# harpscheme.net
KiCad netlist of a schematic drawn in EAGLE
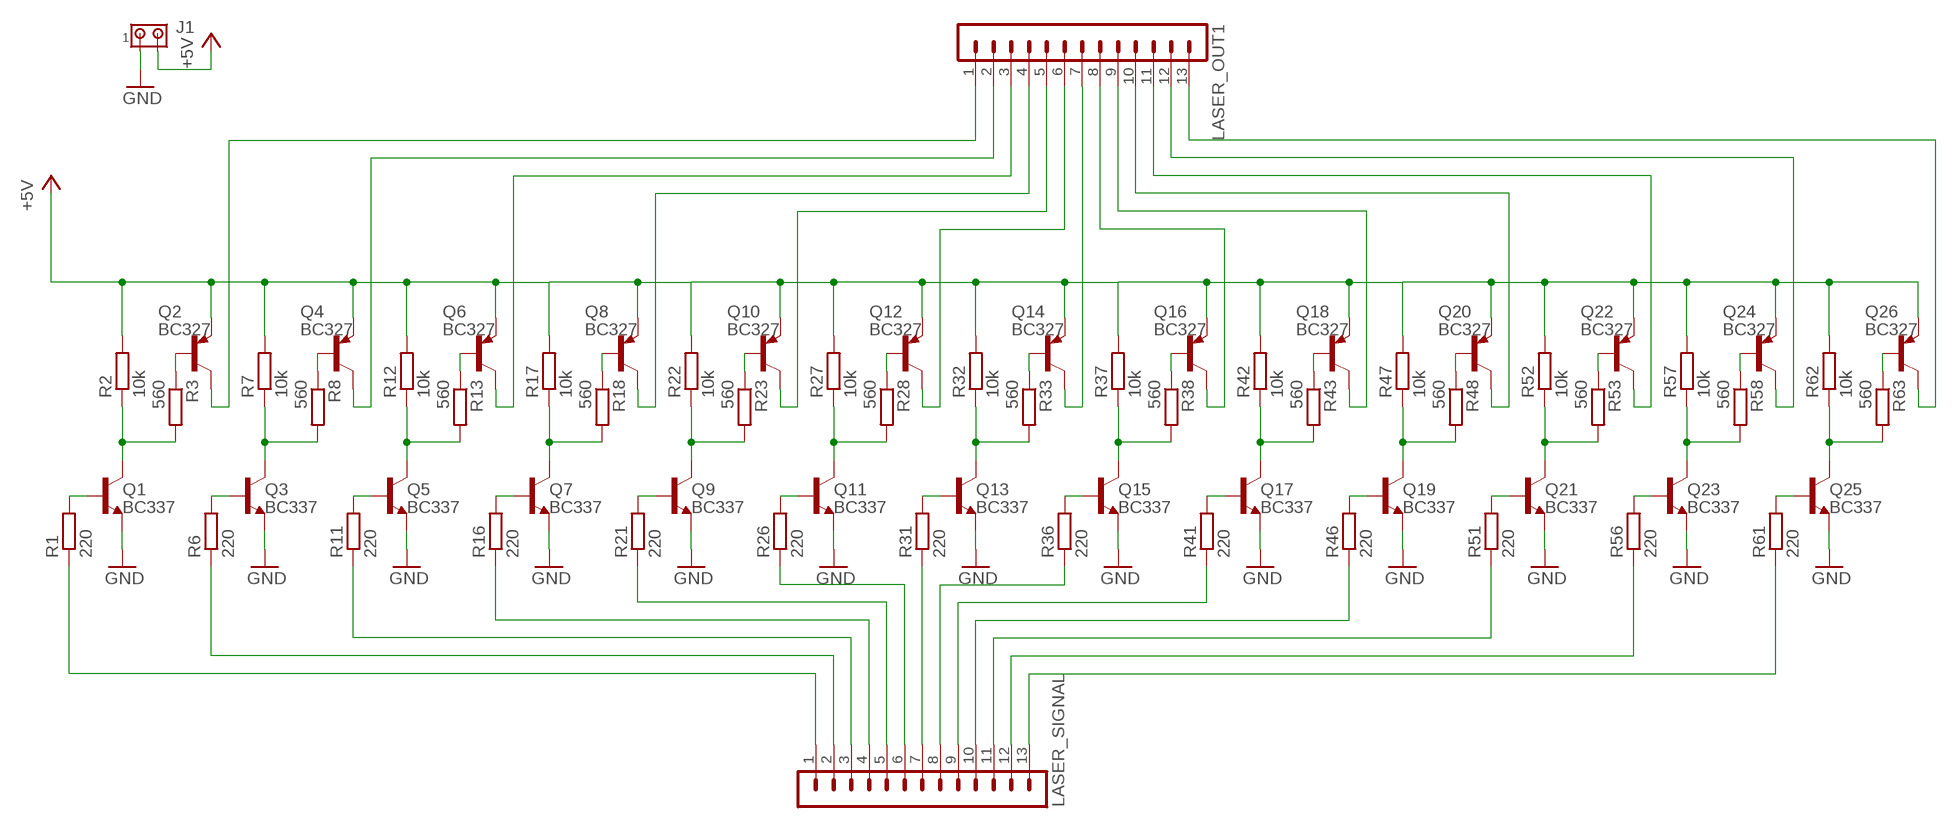
[diagram p0: schematic, sheet 1]

(export (version "E")
  (design (tool "Eeschema 10.0.6"))
  (components
    (comp (ref "J1")
      (value "MTA02-100")
      (footprint "eagle-import:10X02MTA")
      (libsource (lib "eagle-import") (part "MTA02-100"))
    )
    (comp (ref "LASER_OUT1")
      (value "MA13-1")
      (footprint "eagle-import:MA13-1")
      (libsource (lib "eagle-import") (part "MA13-1"))
    )
    (comp (ref "LASER_SIGNAL")
      (value "MA13-1")
      (footprint "eagle-import:MA13-1")
      (libsource (lib "eagle-import") (part "MA13-1"))
    )
    (comp (ref "Q1")
      (value "BC337")
      (footprint "eagle-import:TO92")
      (libsource (lib "eagle-import") (part "BC337"))
    )
    (comp (ref "Q2")
      (value "BC327")
      (footprint "eagle-import:TO92-EBC")
      (libsource (lib "eagle-import") (part "BC327"))
    )
    (comp (ref "Q3")
      (value "BC337")
      (footprint "eagle-import:TO92")
      (libsource (lib "eagle-import") (part "BC337"))
    )
    (comp (ref "Q4")
      (value "BC327")
      (footprint "eagle-import:TO92-EBC")
      (libsource (lib "eagle-import") (part "BC327"))
    )
    (comp (ref "Q5")
      (value "BC337")
      (footprint "eagle-import:TO92")
      (libsource (lib "eagle-import") (part "BC337"))
    )
    (comp (ref "Q6")
      (value "BC327")
      (footprint "eagle-import:TO92-EBC")
      (libsource (lib "eagle-import") (part "BC327"))
    )
    (comp (ref "Q7")
      (value "BC337")
      (footprint "eagle-import:TO92")
      (libsource (lib "eagle-import") (part "BC337"))
    )
    (comp (ref "Q8")
      (value "BC327")
      (footprint "eagle-import:TO92-EBC")
      (libsource (lib "eagle-import") (part "BC327"))
    )
    (comp (ref "Q9")
      (value "BC337")
      (footprint "eagle-import:TO92")
      (libsource (lib "eagle-import") (part "BC337"))
    )
    (comp (ref "Q10")
      (value "BC327")
      (footprint "eagle-import:TO92-EBC")
      (libsource (lib "eagle-import") (part "BC327"))
    )
    (comp (ref "Q11")
      (value "BC337")
      (footprint "eagle-import:TO92")
      (libsource (lib "eagle-import") (part "BC337"))
    )
    (comp (ref "Q12")
      (value "BC327")
      (footprint "eagle-import:TO92-EBC")
      (libsource (lib "eagle-import") (part "BC327"))
    )
    (comp (ref "Q13")
      (value "BC337")
      (footprint "eagle-import:TO92")
      (libsource (lib "eagle-import") (part "BC337"))
    )
    (comp (ref "Q14")
      (value "BC327")
      (footprint "eagle-import:TO92-EBC")
      (libsource (lib "eagle-import") (part "BC327"))
    )
    (comp (ref "Q15")
      (value "BC337")
      (footprint "eagle-import:TO92")
      (libsource (lib "eagle-import") (part "BC337"))
    )
    (comp (ref "Q16")
      (value "BC327")
      (footprint "eagle-import:TO92-EBC")
      (libsource (lib "eagle-import") (part "BC327"))
    )
    (comp (ref "Q17")
      (value "BC337")
      (footprint "eagle-import:TO92")
      (libsource (lib "eagle-import") (part "BC337"))
    )
    (comp (ref "Q18")
      (value "BC327")
      (footprint "eagle-import:TO92-EBC")
      (libsource (lib "eagle-import") (part "BC327"))
    )
    (comp (ref "Q19")
      (value "BC337")
      (footprint "eagle-import:TO92")
      (libsource (lib "eagle-import") (part "BC337"))
    )
    (comp (ref "Q20")
      (value "BC327")
      (footprint "eagle-import:TO92-EBC")
      (libsource (lib "eagle-import") (part "BC327"))
    )
    (comp (ref "Q21")
      (value "BC337")
      (footprint "eagle-import:TO92")
      (libsource (lib "eagle-import") (part "BC337"))
    )
    (comp (ref "Q22")
      (value "BC327")
      (footprint "eagle-import:TO92-EBC")
      (libsource (lib "eagle-import") (part "BC327"))
    )
    (comp (ref "Q23")
      (value "BC337")
      (footprint "eagle-import:TO92")
      (libsource (lib "eagle-import") (part "BC337"))
    )
    (comp (ref "Q24")
      (value "BC327")
      (footprint "eagle-import:TO92-EBC")
      (libsource (lib "eagle-import") (part "BC327"))
    )
    (comp (ref "Q25")
      (value "BC337")
      (footprint "eagle-import:TO92")
      (libsource (lib "eagle-import") (part "BC337"))
    )
    (comp (ref "Q26")
      (value "BC327")
      (footprint "eagle-import:TO92-EBC")
      (libsource (lib "eagle-import") (part "BC327"))
    )
    (comp (ref "R1")
      (value "220")
      (footprint "eagle-import:0207_7")
      (libsource (lib "eagle-import") (part "R-EU_0207/7"))
    )
    (comp (ref "R2")
      (value "10k")
      (footprint "eagle-import:0207_7")
      (libsource (lib "eagle-import") (part "R-EU_0207/7"))
    )
    (comp (ref "R3")
      (value "560")
      (footprint "eagle-import:0207_7")
      (libsource (lib "eagle-import") (part "R-EU_0207/7"))
    )
    (comp (ref "R6")
      (value "220")
      (footprint "eagle-import:0207_7")
      (libsource (lib "eagle-import") (part "R-EU_0207/7"))
    )
    (comp (ref "R7")
      (value "10k")
      (footprint "eagle-import:0207_7")
      (libsource (lib "eagle-import") (part "R-EU_0207/7"))
    )
    (comp (ref "R8")
      (value "560")
      (footprint "eagle-import:0207_7")
      (libsource (lib "eagle-import") (part "R-EU_0207/7"))
    )
    (comp (ref "R11")
      (value "220")
      (footprint "eagle-import:0207_7")
      (libsource (lib "eagle-import") (part "R-EU_0207/7"))
    )
    (comp (ref "R12")
      (value "10k")
      (footprint "eagle-import:0207_7")
      (libsource (lib "eagle-import") (part "R-EU_0207/7"))
    )
    (comp (ref "R13")
      (value "560")
      (footprint "eagle-import:0207_7")
      (libsource (lib "eagle-import") (part "R-EU_0207/7"))
    )
    (comp (ref "R16")
      (value "220")
      (footprint "eagle-import:0207_7")
      (libsource (lib "eagle-import") (part "R-EU_0207/7"))
    )
    (comp (ref "R17")
      (value "10k")
      (footprint "eagle-import:0207_7")
      (libsource (lib "eagle-import") (part "R-EU_0207/7"))
    )
    (comp (ref "R18")
      (value "560")
      (footprint "eagle-import:0207_7")
      (libsource (lib "eagle-import") (part "R-EU_0207/7"))
    )
    (comp (ref "R21")
      (value "220")
      (footprint "eagle-import:0207_7")
      (libsource (lib "eagle-import") (part "R-EU_0207/7"))
    )
    (comp (ref "R22")
      (value "10k")
      (footprint "eagle-import:0207_7")
      (libsource (lib "eagle-import") (part "R-EU_0207/7"))
    )
    (comp (ref "R23")
      (value "560")
      (footprint "eagle-import:0207_7")
      (libsource (lib "eagle-import") (part "R-EU_0207/7"))
    )
    (comp (ref "R26")
      (value "220")
      (footprint "eagle-import:0207_7")
      (libsource (lib "eagle-import") (part "R-EU_0207/7"))
    )
    (comp (ref "R27")
      (value "10k")
      (footprint "eagle-import:0207_7")
      (libsource (lib "eagle-import") (part "R-EU_0207/7"))
    )
    (comp (ref "R28")
      (value "560")
      (footprint "eagle-import:0207_7")
      (libsource (lib "eagle-import") (part "R-EU_0207/7"))
    )
    (comp (ref "R31")
      (value "220")
      (footprint "eagle-import:0207_7")
      (libsource (lib "eagle-import") (part "R-EU_0207/7"))
    )
    (comp (ref "R32")
      (value "10k")
      (footprint "eagle-import:0207_7")
      (libsource (lib "eagle-import") (part "R-EU_0207/7"))
    )
    (comp (ref "R33")
      (value "560")
      (footprint "eagle-import:0207_7")
      (libsource (lib "eagle-import") (part "R-EU_0207/7"))
    )
    (comp (ref "R36")
      (value "220")
      (footprint "eagle-import:0207_7")
      (libsource (lib "eagle-import") (part "R-EU_0207/7"))
    )
    (comp (ref "R37")
      (value "10k")
      (footprint "eagle-import:0207_7")
      (libsource (lib "eagle-import") (part "R-EU_0207/7"))
    )
    (comp (ref "R38")
      (value "560")
      (footprint "eagle-import:0207_7")
      (libsource (lib "eagle-import") (part "R-EU_0207/7"))
    )
    (comp (ref "R41")
      (value "220")
      (footprint "eagle-import:0207_7")
      (libsource (lib "eagle-import") (part "R-EU_0207/7"))
    )
    (comp (ref "R42")
      (value "10k")
      (footprint "eagle-import:0207_7")
      (libsource (lib "eagle-import") (part "R-EU_0207/7"))
    )
    (comp (ref "R43")
      (value "560")
      (footprint "eagle-import:0207_7")
      (libsource (lib "eagle-import") (part "R-EU_0207/7"))
    )
    (comp (ref "R46")
      (value "220")
      (footprint "eagle-import:0207_7")
      (libsource (lib "eagle-import") (part "R-EU_0207/7"))
    )
    (comp (ref "R47")
      (value "10k")
      (footprint "eagle-import:0207_7")
      (libsource (lib "eagle-import") (part "R-EU_0207/7"))
    )
    (comp (ref "R48")
      (value "560")
      (footprint "eagle-import:0207_7")
      (libsource (lib "eagle-import") (part "R-EU_0207/7"))
    )
    (comp (ref "R51")
      (value "220")
      (footprint "eagle-import:0207_7")
      (libsource (lib "eagle-import") (part "R-EU_0207/7"))
    )
    (comp (ref "R52")
      (value "10k")
      (footprint "eagle-import:0207_7")
      (libsource (lib "eagle-import") (part "R-EU_0207/7"))
    )
    (comp (ref "R53")
      (value "560")
      (footprint "eagle-import:0207_7")
      (libsource (lib "eagle-import") (part "R-EU_0207/7"))
    )
    (comp (ref "R56")
      (value "220")
      (footprint "eagle-import:0207_7")
      (libsource (lib "eagle-import") (part "R-EU_0207/7"))
    )
    (comp (ref "R57")
      (value "10k")
      (footprint "eagle-import:0207_7")
      (libsource (lib "eagle-import") (part "R-EU_0207/7"))
    )
    (comp (ref "R58")
      (value "560")
      (footprint "eagle-import:0207_7")
      (libsource (lib "eagle-import") (part "R-EU_0207/7"))
    )
    (comp (ref "R61")
      (value "220")
      (footprint "eagle-import:0207_7")
      (libsource (lib "eagle-import") (part "R-EU_0207/7"))
    )
    (comp (ref "R62")
      (value "10k")
      (footprint "eagle-import:0207_7")
      (libsource (lib "eagle-import") (part "R-EU_0207/7"))
    )
    (comp (ref "R63")
      (value "560")
      (footprint "eagle-import:0207_7")
      (libsource (lib "eagle-import") (part "R-EU_0207/7"))
    )
  )
  (nets
    (net (code "1") (name "+5V") (class "Default")
      (node (ref "J1") (pin "2") (pinfunction "2_2") (pintype "passive"))
      (node (ref "Q10") (pin "E") (pinfunction "E_E") (pintype "passive"))
      (node (ref "Q12") (pin "E") (pinfunction "E_E") (pintype "passive"))
      (node (ref "Q14") (pin "E") (pinfunction "E_E") (pintype "passive"))
      (node (ref "Q16") (pin "E") (pinfunction "E_E") (pintype "passive"))
      (node (ref "Q18") (pin "E") (pinfunction "E_E") (pintype "passive"))
      (node (ref "Q2") (pin "E") (pinfunction "E_E") (pintype "passive"))
      (node (ref "Q20") (pin "E") (pinfunction "E_E") (pintype "passive"))
      (node (ref "Q22") (pin "E") (pinfunction "E_E") (pintype "passive"))
      (node (ref "Q24") (pin "E") (pinfunction "E_E") (pintype "passive"))
      (node (ref "Q26") (pin "E") (pinfunction "E_E") (pintype "passive"))
      (node (ref "Q4") (pin "E") (pinfunction "E_E") (pintype "passive"))
      (node (ref "Q6") (pin "E") (pinfunction "E_E") (pintype "passive"))
      (node (ref "Q8") (pin "E") (pinfunction "E_E") (pintype "passive"))
      (node (ref "R12") (pin "2") (pinfunction "2_2") (pintype "passive"))
      (node (ref "R17") (pin "2") (pinfunction "2_2") (pintype "passive"))
      (node (ref "R2") (pin "2") (pinfunction "2_2") (pintype "passive"))
      (node (ref "R22") (pin "2") (pinfunction "2_2") (pintype "passive"))
      (node (ref "R27") (pin "2") (pinfunction "2_2") (pintype "passive"))
      (node (ref "R32") (pin "2") (pinfunction "2_2") (pintype "passive"))
      (node (ref "R37") (pin "2") (pinfunction "2_2") (pintype "passive"))
      (node (ref "R42") (pin "2") (pinfunction "2_2") (pintype "passive"))
      (node (ref "R47") (pin "2") (pinfunction "2_2") (pintype "passive"))
      (node (ref "R52") (pin "2") (pinfunction "2_2") (pintype "passive"))
      (node (ref "R57") (pin "2") (pinfunction "2_2") (pintype "passive"))
      (node (ref "R62") (pin "2") (pinfunction "2_2") (pintype "passive"))
      (node (ref "R7") (pin "2") (pinfunction "2_2") (pintype "passive"))
    )
    (net (code "2") (name "GND") (class "Default")
      (node (ref "J1") (pin "1") (pinfunction "1_1") (pintype "passive"))
      (node (ref "Q1") (pin "1") (pinfunction "E_1") (pintype "passive"))
      (node (ref "Q11") (pin "1") (pinfunction "E_1") (pintype "passive"))
      (node (ref "Q13") (pin "1") (pinfunction "E_1") (pintype "passive"))
      (node (ref "Q15") (pin "1") (pinfunction "E_1") (pintype "passive"))
      (node (ref "Q17") (pin "1") (pinfunction "E_1") (pintype "passive"))
      (node (ref "Q19") (pin "1") (pinfunction "E_1") (pintype "passive"))
      (node (ref "Q21") (pin "1") (pinfunction "E_1") (pintype "passive"))
      (node (ref "Q23") (pin "1") (pinfunction "E_1") (pintype "passive"))
      (node (ref "Q25") (pin "1") (pinfunction "E_1") (pintype "passive"))
      (node (ref "Q3") (pin "1") (pinfunction "E_1") (pintype "passive"))
      (node (ref "Q5") (pin "1") (pinfunction "E_1") (pintype "passive"))
      (node (ref "Q7") (pin "1") (pinfunction "E_1") (pintype "passive"))
      (node (ref "Q9") (pin "1") (pinfunction "E_1") (pintype "passive"))
    )
    (net (code "3") (name "Net-(LASER_OUT1-Pad1)") (class "Default")
      (node (ref "LASER_OUT1") (pin "1") (pinfunction "1_1") (pintype "passive"))
      (node (ref "Q2") (pin "C") (pinfunction "C_C") (pintype "passive"))
    )
    (net (code "4") (name "Net-(LASER_OUT1-Pad2)") (class "Default")
      (node (ref "LASER_OUT1") (pin "2") (pinfunction "2_2") (pintype "passive"))
      (node (ref "Q4") (pin "C") (pinfunction "C_C") (pintype "passive"))
    )
    (net (code "5") (name "Net-(LASER_OUT1-Pad3)") (class "Default")
      (node (ref "LASER_OUT1") (pin "3") (pinfunction "3_3") (pintype "passive"))
      (node (ref "Q6") (pin "C") (pinfunction "C_C") (pintype "passive"))
    )
    (net (code "6") (name "Net-(LASER_OUT1-Pad4)") (class "Default")
      (node (ref "LASER_OUT1") (pin "4") (pinfunction "4_4") (pintype "passive"))
      (node (ref "Q8") (pin "C") (pinfunction "C_C") (pintype "passive"))
    )
    (net (code "7") (name "Net-(LASER_OUT1-Pad5)") (class "Default")
      (node (ref "LASER_OUT1") (pin "5") (pinfunction "5_5") (pintype "passive"))
      (node (ref "Q10") (pin "C") (pinfunction "C_C") (pintype "passive"))
    )
    (net (code "8") (name "Net-(LASER_OUT1-Pad6)") (class "Default")
      (node (ref "LASER_OUT1") (pin "6") (pinfunction "6_6") (pintype "passive"))
      (node (ref "Q12") (pin "C") (pinfunction "C_C") (pintype "passive"))
    )
    (net (code "9") (name "Net-(LASER_OUT1-Pad7)") (class "Default")
      (node (ref "LASER_OUT1") (pin "7") (pinfunction "7_7") (pintype "passive"))
      (node (ref "Q14") (pin "C") (pinfunction "C_C") (pintype "passive"))
    )
    (net (code "10") (name "Net-(LASER_OUT1-Pad8)") (class "Default")
      (node (ref "LASER_OUT1") (pin "8") (pinfunction "8_8") (pintype "passive"))
      (node (ref "Q16") (pin "C") (pinfunction "C_C") (pintype "passive"))
    )
    (net (code "11") (name "Net-(LASER_OUT1-Pad9)") (class "Default")
      (node (ref "LASER_OUT1") (pin "9") (pinfunction "9_9") (pintype "passive"))
      (node (ref "Q18") (pin "C") (pinfunction "C_C") (pintype "passive"))
    )
    (net (code "12") (name "Net-(LASER_OUT1-Pad10)") (class "Default")
      (node (ref "LASER_OUT1") (pin "10") (pinfunction "10_10") (pintype "passive"))
      (node (ref "Q20") (pin "C") (pinfunction "C_C") (pintype "passive"))
    )
    (net (code "13") (name "Net-(LASER_OUT1-Pad11)") (class "Default")
      (node (ref "LASER_OUT1") (pin "11") (pinfunction "11_11") (pintype "passive"))
      (node (ref "Q22") (pin "C") (pinfunction "C_C") (pintype "passive"))
    )
    (net (code "14") (name "Net-(LASER_OUT1-Pad12)") (class "Default")
      (node (ref "LASER_OUT1") (pin "12") (pinfunction "12_12") (pintype "passive"))
      (node (ref "Q24") (pin "C") (pinfunction "C_C") (pintype "passive"))
    )
    (net (code "15") (name "Net-(LASER_OUT1-Pad13)") (class "Default")
      (node (ref "LASER_OUT1") (pin "13") (pinfunction "13_13") (pintype "passive"))
      (node (ref "Q26") (pin "C") (pinfunction "C_C") (pintype "passive"))
    )
    (net (code "16") (name "Net-(LASER_SIGNAL-Pad1)") (class "Default")
      (node (ref "LASER_SIGNAL") (pin "1") (pinfunction "1_1") (pintype "passive"))
      (node (ref "R1") (pin "1") (pinfunction "1_1") (pintype "passive"))
    )
    (net (code "17") (name "Net-(LASER_SIGNAL-Pad2)") (class "Default")
      (node (ref "LASER_SIGNAL") (pin "2") (pinfunction "2_2") (pintype "passive"))
      (node (ref "R6") (pin "1") (pinfunction "1_1") (pintype "passive"))
    )
    (net (code "18") (name "Net-(LASER_SIGNAL-Pad3)") (class "Default")
      (node (ref "LASER_SIGNAL") (pin "3") (pinfunction "3_3") (pintype "passive"))
      (node (ref "R11") (pin "1") (pinfunction "1_1") (pintype "passive"))
    )
    (net (code "19") (name "Net-(LASER_SIGNAL-Pad4)") (class "Default")
      (node (ref "LASER_SIGNAL") (pin "4") (pinfunction "4_4") (pintype "passive"))
      (node (ref "R16") (pin "1") (pinfunction "1_1") (pintype "passive"))
    )
    (net (code "20") (name "Net-(LASER_SIGNAL-Pad5)") (class "Default")
      (node (ref "LASER_SIGNAL") (pin "5") (pinfunction "5_5") (pintype "passive"))
      (node (ref "R21") (pin "1") (pinfunction "1_1") (pintype "passive"))
    )
    (net (code "21") (name "Net-(LASER_SIGNAL-Pad6)") (class "Default")
      (node (ref "LASER_SIGNAL") (pin "6") (pinfunction "6_6") (pintype "passive"))
      (node (ref "R26") (pin "1") (pinfunction "1_1") (pintype "passive"))
    )
    (net (code "22") (name "Net-(LASER_SIGNAL-Pad7)") (class "Default")
      (node (ref "LASER_SIGNAL") (pin "7") (pinfunction "7_7") (pintype "passive"))
      (node (ref "R31") (pin "1") (pinfunction "1_1") (pintype "passive"))
    )
    (net (code "23") (name "Net-(LASER_SIGNAL-Pad8)") (class "Default")
      (node (ref "LASER_SIGNAL") (pin "8") (pinfunction "8_8") (pintype "passive"))
      (node (ref "R36") (pin "1") (pinfunction "1_1") (pintype "passive"))
    )
    (net (code "24") (name "Net-(LASER_SIGNAL-Pad9)") (class "Default")
      (node (ref "LASER_SIGNAL") (pin "9") (pinfunction "9_9") (pintype "passive"))
      (node (ref "R41") (pin "1") (pinfunction "1_1") (pintype "passive"))
    )
    (net (code "25") (name "Net-(LASER_SIGNAL-Pad10)") (class "Default")
      (node (ref "LASER_SIGNAL") (pin "10") (pinfunction "10_10") (pintype "passive"))
      (node (ref "R46") (pin "1") (pinfunction "1_1") (pintype "passive"))
    )
    (net (code "26") (name "Net-(LASER_SIGNAL-Pad11)") (class "Default")
      (node (ref "LASER_SIGNAL") (pin "11") (pinfunction "11_11") (pintype "passive"))
      (node (ref "R51") (pin "1") (pinfunction "1_1") (pintype "passive"))
    )
    (net (code "27") (name "Net-(LASER_SIGNAL-Pad12)") (class "Default")
      (node (ref "LASER_SIGNAL") (pin "12") (pinfunction "12_12") (pintype "passive"))
      (node (ref "R56") (pin "1") (pinfunction "1_1") (pintype "passive"))
    )
    (net (code "28") (name "Net-(LASER_SIGNAL-Pad13)") (class "Default")
      (node (ref "LASER_SIGNAL") (pin "13") (pinfunction "13_13") (pintype "passive"))
      (node (ref "R61") (pin "1") (pinfunction "1_1") (pintype "passive"))
    )
    (net (code "29") (name "Net-(Q1-B)") (class "Default")
      (node (ref "Q1") (pin "2") (pinfunction "B_2") (pintype "passive"))
      (node (ref "R1") (pin "2") (pinfunction "2_2") (pintype "passive"))
    )
    (net (code "30") (name "Net-(Q1-C)") (class "Default")
      (node (ref "Q1") (pin "3") (pinfunction "C_3") (pintype "passive"))
      (node (ref "R2") (pin "1") (pinfunction "1_1") (pintype "passive"))
      (node (ref "R3") (pin "2") (pinfunction "2_2") (pintype "passive"))
    )
    (net (code "31") (name "Net-(Q2-PadB)") (class "Default")
      (node (ref "Q2") (pin "B") (pinfunction "B_B") (pintype "passive"))
      (node (ref "R3") (pin "1") (pinfunction "1_1") (pintype "passive"))
    )
    (net (code "32") (name "Net-(Q3-B)") (class "Default")
      (node (ref "Q3") (pin "2") (pinfunction "B_2") (pintype "passive"))
      (node (ref "R6") (pin "2") (pinfunction "2_2") (pintype "passive"))
    )
    (net (code "33") (name "Net-(Q3-C)") (class "Default")
      (node (ref "Q3") (pin "3") (pinfunction "C_3") (pintype "passive"))
      (node (ref "R7") (pin "1") (pinfunction "1_1") (pintype "passive"))
      (node (ref "R8") (pin "2") (pinfunction "2_2") (pintype "passive"))
    )
    (net (code "34") (name "Net-(Q4-PadB)") (class "Default")
      (node (ref "Q4") (pin "B") (pinfunction "B_B") (pintype "passive"))
      (node (ref "R8") (pin "1") (pinfunction "1_1") (pintype "passive"))
    )
    (net (code "35") (name "Net-(Q5-B)") (class "Default")
      (node (ref "Q5") (pin "2") (pinfunction "B_2") (pintype "passive"))
      (node (ref "R11") (pin "2") (pinfunction "2_2") (pintype "passive"))
    )
    (net (code "36") (name "Net-(Q5-C)") (class "Default")
      (node (ref "Q5") (pin "3") (pinfunction "C_3") (pintype "passive"))
      (node (ref "R12") (pin "1") (pinfunction "1_1") (pintype "passive"))
      (node (ref "R13") (pin "2") (pinfunction "2_2") (pintype "passive"))
    )
    (net (code "37") (name "Net-(Q6-PadB)") (class "Default")
      (node (ref "Q6") (pin "B") (pinfunction "B_B") (pintype "passive"))
      (node (ref "R13") (pin "1") (pinfunction "1_1") (pintype "passive"))
    )
    (net (code "38") (name "Net-(Q7-B)") (class "Default")
      (node (ref "Q7") (pin "2") (pinfunction "B_2") (pintype "passive"))
      (node (ref "R16") (pin "2") (pinfunction "2_2") (pintype "passive"))
    )
    (net (code "39") (name "Net-(Q7-C)") (class "Default")
      (node (ref "Q7") (pin "3") (pinfunction "C_3") (pintype "passive"))
      (node (ref "R17") (pin "1") (pinfunction "1_1") (pintype "passive"))
      (node (ref "R18") (pin "2") (pinfunction "2_2") (pintype "passive"))
    )
    (net (code "40") (name "Net-(Q8-PadB)") (class "Default")
      (node (ref "Q8") (pin "B") (pinfunction "B_B") (pintype "passive"))
      (node (ref "R18") (pin "1") (pinfunction "1_1") (pintype "passive"))
    )
    (net (code "41") (name "Net-(Q9-B)") (class "Default")
      (node (ref "Q9") (pin "2") (pinfunction "B_2") (pintype "passive"))
      (node (ref "R21") (pin "2") (pinfunction "2_2") (pintype "passive"))
    )
    (net (code "42") (name "Net-(Q9-C)") (class "Default")
      (node (ref "Q9") (pin "3") (pinfunction "C_3") (pintype "passive"))
      (node (ref "R22") (pin "1") (pinfunction "1_1") (pintype "passive"))
      (node (ref "R23") (pin "2") (pinfunction "2_2") (pintype "passive"))
    )
    (net (code "43") (name "Net-(Q10-PadB)") (class "Default")
      (node (ref "Q10") (pin "B") (pinfunction "B_B") (pintype "passive"))
      (node (ref "R23") (pin "1") (pinfunction "1_1") (pintype "passive"))
    )
    (net (code "44") (name "Net-(Q11-B)") (class "Default")
      (node (ref "Q11") (pin "2") (pinfunction "B_2") (pintype "passive"))
      (node (ref "R26") (pin "2") (pinfunction "2_2") (pintype "passive"))
    )
    (net (code "45") (name "Net-(Q11-C)") (class "Default")
      (node (ref "Q11") (pin "3") (pinfunction "C_3") (pintype "passive"))
      (node (ref "R27") (pin "1") (pinfunction "1_1") (pintype "passive"))
      (node (ref "R28") (pin "2") (pinfunction "2_2") (pintype "passive"))
    )
    (net (code "46") (name "Net-(Q12-PadB)") (class "Default")
      (node (ref "Q12") (pin "B") (pinfunction "B_B") (pintype "passive"))
      (node (ref "R28") (pin "1") (pinfunction "1_1") (pintype "passive"))
    )
    (net (code "47") (name "Net-(Q13-B)") (class "Default")
      (node (ref "Q13") (pin "2") (pinfunction "B_2") (pintype "passive"))
      (node (ref "R31") (pin "2") (pinfunction "2_2") (pintype "passive"))
    )
    (net (code "48") (name "Net-(Q13-C)") (class "Default")
      (node (ref "Q13") (pin "3") (pinfunction "C_3") (pintype "passive"))
      (node (ref "R32") (pin "1") (pinfunction "1_1") (pintype "passive"))
      (node (ref "R33") (pin "2") (pinfunction "2_2") (pintype "passive"))
    )
    (net (code "49") (name "Net-(Q14-PadB)") (class "Default")
      (node (ref "Q14") (pin "B") (pinfunction "B_B") (pintype "passive"))
      (node (ref "R33") (pin "1") (pinfunction "1_1") (pintype "passive"))
    )
    (net (code "50") (name "Net-(Q15-B)") (class "Default")
      (node (ref "Q15") (pin "2") (pinfunction "B_2") (pintype "passive"))
      (node (ref "R36") (pin "2") (pinfunction "2_2") (pintype "passive"))
    )
    (net (code "51") (name "Net-(Q15-C)") (class "Default")
      (node (ref "Q15") (pin "3") (pinfunction "C_3") (pintype "passive"))
      (node (ref "R37") (pin "1") (pinfunction "1_1") (pintype "passive"))
      (node (ref "R38") (pin "2") (pinfunction "2_2") (pintype "passive"))
    )
    (net (code "52") (name "Net-(Q16-PadB)") (class "Default")
      (node (ref "Q16") (pin "B") (pinfunction "B_B") (pintype "passive"))
      (node (ref "R38") (pin "1") (pinfunction "1_1") (pintype "passive"))
    )
    (net (code "53") (name "Net-(Q17-B)") (class "Default")
      (node (ref "Q17") (pin "2") (pinfunction "B_2") (pintype "passive"))
      (node (ref "R41") (pin "2") (pinfunction "2_2") (pintype "passive"))
    )
    (net (code "54") (name "Net-(Q17-C)") (class "Default")
      (node (ref "Q17") (pin "3") (pinfunction "C_3") (pintype "passive"))
      (node (ref "R42") (pin "1") (pinfunction "1_1") (pintype "passive"))
      (node (ref "R43") (pin "2") (pinfunction "2_2") (pintype "passive"))
    )
    (net (code "55") (name "Net-(Q18-PadB)") (class "Default")
      (node (ref "Q18") (pin "B") (pinfunction "B_B") (pintype "passive"))
      (node (ref "R43") (pin "1") (pinfunction "1_1") (pintype "passive"))
    )
    (net (code "56") (name "Net-(Q19-B)") (class "Default")
      (node (ref "Q19") (pin "2") (pinfunction "B_2") (pintype "passive"))
      (node (ref "R46") (pin "2") (pinfunction "2_2") (pintype "passive"))
    )
    (net (code "57") (name "Net-(Q19-C)") (class "Default")
      (node (ref "Q19") (pin "3") (pinfunction "C_3") (pintype "passive"))
      (node (ref "R47") (pin "1") (pinfunction "1_1") (pintype "passive"))
      (node (ref "R48") (pin "2") (pinfunction "2_2") (pintype "passive"))
    )
    (net (code "58") (name "Net-(Q20-PadB)") (class "Default")
      (node (ref "Q20") (pin "B") (pinfunction "B_B") (pintype "passive"))
      (node (ref "R48") (pin "1") (pinfunction "1_1") (pintype "passive"))
    )
    (net (code "59") (name "Net-(Q21-B)") (class "Default")
      (node (ref "Q21") (pin "2") (pinfunction "B_2") (pintype "passive"))
      (node (ref "R51") (pin "2") (pinfunction "2_2") (pintype "passive"))
    )
    (net (code "60") (name "Net-(Q21-C)") (class "Default")
      (node (ref "Q21") (pin "3") (pinfunction "C_3") (pintype "passive"))
      (node (ref "R52") (pin "1") (pinfunction "1_1") (pintype "passive"))
      (node (ref "R53") (pin "2") (pinfunction "2_2") (pintype "passive"))
    )
    (net (code "61") (name "Net-(Q22-PadB)") (class "Default")
      (node (ref "Q22") (pin "B") (pinfunction "B_B") (pintype "passive"))
      (node (ref "R53") (pin "1") (pinfunction "1_1") (pintype "passive"))
    )
    (net (code "62") (name "Net-(Q23-B)") (class "Default")
      (node (ref "Q23") (pin "2") (pinfunction "B_2") (pintype "passive"))
      (node (ref "R56") (pin "2") (pinfunction "2_2") (pintype "passive"))
    )
    (net (code "63") (name "Net-(Q23-C)") (class "Default")
      (node (ref "Q23") (pin "3") (pinfunction "C_3") (pintype "passive"))
      (node (ref "R57") (pin "1") (pinfunction "1_1") (pintype "passive"))
      (node (ref "R58") (pin "2") (pinfunction "2_2") (pintype "passive"))
    )
    (net (code "64") (name "Net-(Q24-PadB)") (class "Default")
      (node (ref "Q24") (pin "B") (pinfunction "B_B") (pintype "passive"))
      (node (ref "R58") (pin "1") (pinfunction "1_1") (pintype "passive"))
    )
    (net (code "65") (name "Net-(Q25-B)") (class "Default")
      (node (ref "Q25") (pin "2") (pinfunction "B_2") (pintype "passive"))
      (node (ref "R61") (pin "2") (pinfunction "2_2") (pintype "passive"))
    )
    (net (code "66") (name "Net-(Q25-C)") (class "Default")
      (node (ref "Q25") (pin "3") (pinfunction "C_3") (pintype "passive"))
      (node (ref "R62") (pin "1") (pinfunction "1_1") (pintype "passive"))
      (node (ref "R63") (pin "2") (pinfunction "2_2") (pintype "passive"))
    )
    (net (code "67") (name "Net-(Q26-PadB)") (class "Default")
      (node (ref "Q26") (pin "B") (pinfunction "B_B") (pintype "passive"))
      (node (ref "R63") (pin "1") (pinfunction "1_1") (pintype "passive"))
    )
  )
)
